# BigBooster.net
KiCad netlist of a schematic drawn in Altium Designer
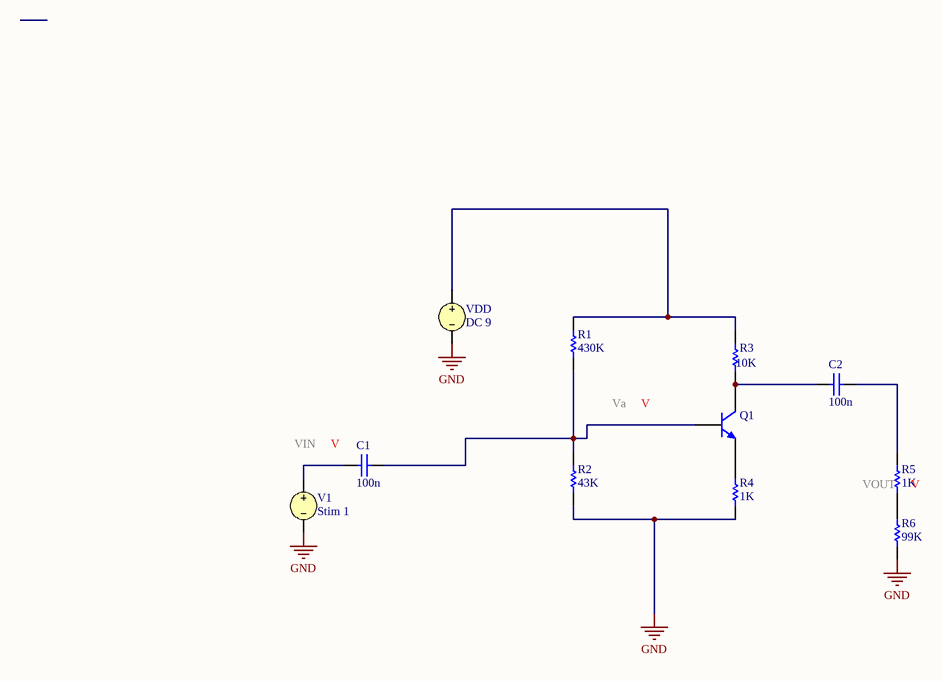
[diagram p0: BigBooster.SchDoc]

(export (version "E")
  (design (tool "Eeschema 10.0.6"))
  (components
    (comp (ref "C1")
      (value "100n")
      (description "Capacitor")
      (libsource (lib "Simulation Generic Components") (part "Capacitor"))
    )
    (comp (ref "C2")
      (value "100n")
      (description "Capacitor")
      (libsource (lib "Simulation Generic Components") (part "Capacitor"))
    )
    (comp (ref "Q1")
      (value "Bipolar NPN 3 Pins Transistor Gummel-Poon Model")
      (libsource (lib "Simulation Generic Components") (part "BJT NPN_GP"))
    )
    (comp (ref "R1")
      (value "430K")
      (description "Resistor")
      (libsource (lib "Simulation Generic Components") (part "Resistor"))
    )
    (comp (ref "R2")
      (value "43K")
      (description "Resistor")
      (libsource (lib "Simulation Generic Components") (part "Resistor"))
    )
    (comp (ref "R3")
      (value "10K")
      (description "Resistor")
      (libsource (lib "Simulation Generic Components") (part "Resistor"))
    )
    (comp (ref "R4")
      (value "1K")
      (description "Resistor")
      (libsource (lib "Simulation Generic Components") (part "Resistor"))
    )
    (comp (ref "R5")
      (value "1K")
      (description "Resistor")
      (libsource (lib "Simulation Generic Components") (part "Resistor"))
    )
    (comp (ref "R6")
      (value "99K")
      (description "Resistor")
      (libsource (lib "Simulation Generic Components") (part "Resistor"))
    )
    (comp (ref "V1")
      (value "Stim 1")
      (description "Voltage Source")
      (fields (field (name "PUBLISHER") "Altium Limited"))
      (libsource (lib "Simulation Generic Components") (part "VSRC"))
    )
    (comp (ref "VDD")
      (value "DC 9")
      (description "Voltage Source")
      (fields (field (name "PUBLISHER") "Altium Limited"))
      (libsource (lib "Simulation Generic Components") (part "VSRC"))
    )
  )
  (nets
    (net (code "1") (name "GND") (class "Default")
      (node (ref "R2") (pin "1") (pinfunction "1_1") (pintype "passive"))
      (node (ref "R4") (pin "1") (pinfunction "1_1") (pintype "passive"))
      (node (ref "R6") (pin "1") (pinfunction "1_1") (pintype "passive"))
      (node (ref "V1") (pin "2") (pinfunction "2_2") (pintype "passive"))
      (node (ref "VDD") (pin "2") (pinfunction "2_2") (pintype "passive"))
    )
    (net (code "2") (name "Net-(C1-Pad1)") (class "Default")
      (node (ref "C1") (pin "1") (pinfunction "1_1") (pintype "passive"))
      (node (ref "V1") (pin "1") (pinfunction "1_1") (pintype "passive"))
    )
    (net (code "3") (name "Net-(C2-Pad2)") (class "Default")
      (node (ref "C2") (pin "2") (pinfunction "2_2") (pintype "passive"))
      (node (ref "R5") (pin "2") (pinfunction "2_2") (pintype "passive"))
    )
    (net (code "4") (name "Net-(Q1-B)") (class "Default")
      (node (ref "C1") (pin "2") (pinfunction "2_2") (pintype "passive"))
      (node (ref "Q1") (pin "2") (pinfunction "B_2") (pintype "passive"))
      (node (ref "R1") (pin "1") (pinfunction "1_1") (pintype "passive"))
      (node (ref "R2") (pin "2") (pinfunction "2_2") (pintype "passive"))
    )
    (net (code "5") (name "Net-(Q1-C)") (class "Default")
      (node (ref "C2") (pin "1") (pinfunction "1_1") (pintype "passive"))
      (node (ref "Q1") (pin "1") (pinfunction "C_1") (pintype "passive"))
      (node (ref "R3") (pin "1") (pinfunction "1_1") (pintype "passive"))
    )
    (net (code "6") (name "Net-(Q1-E)") (class "Default")
      (node (ref "Q1") (pin "3") (pinfunction "E_3") (pintype "passive"))
      (node (ref "R4") (pin "2") (pinfunction "2_2") (pintype "passive"))
    )
    (net (code "7") (name "Net-(R1-Pad2)") (class "Default")
      (node (ref "R1") (pin "2") (pinfunction "2_2") (pintype "passive"))
      (node (ref "R3") (pin "2") (pinfunction "2_2") (pintype "passive"))
      (node (ref "VDD") (pin "1") (pinfunction "1_1") (pintype "passive"))
    )
    (net (code "8") (name "Net-(R5-Pad1)") (class "Default")
      (node (ref "R5") (pin "1") (pinfunction "1_1") (pintype "passive"))
      (node (ref "R6") (pin "2") (pinfunction "2_2") (pintype "passive"))
    )
  )
)
